# Circuit.net
KiCad netlist of a schematic drawn in EAGLE
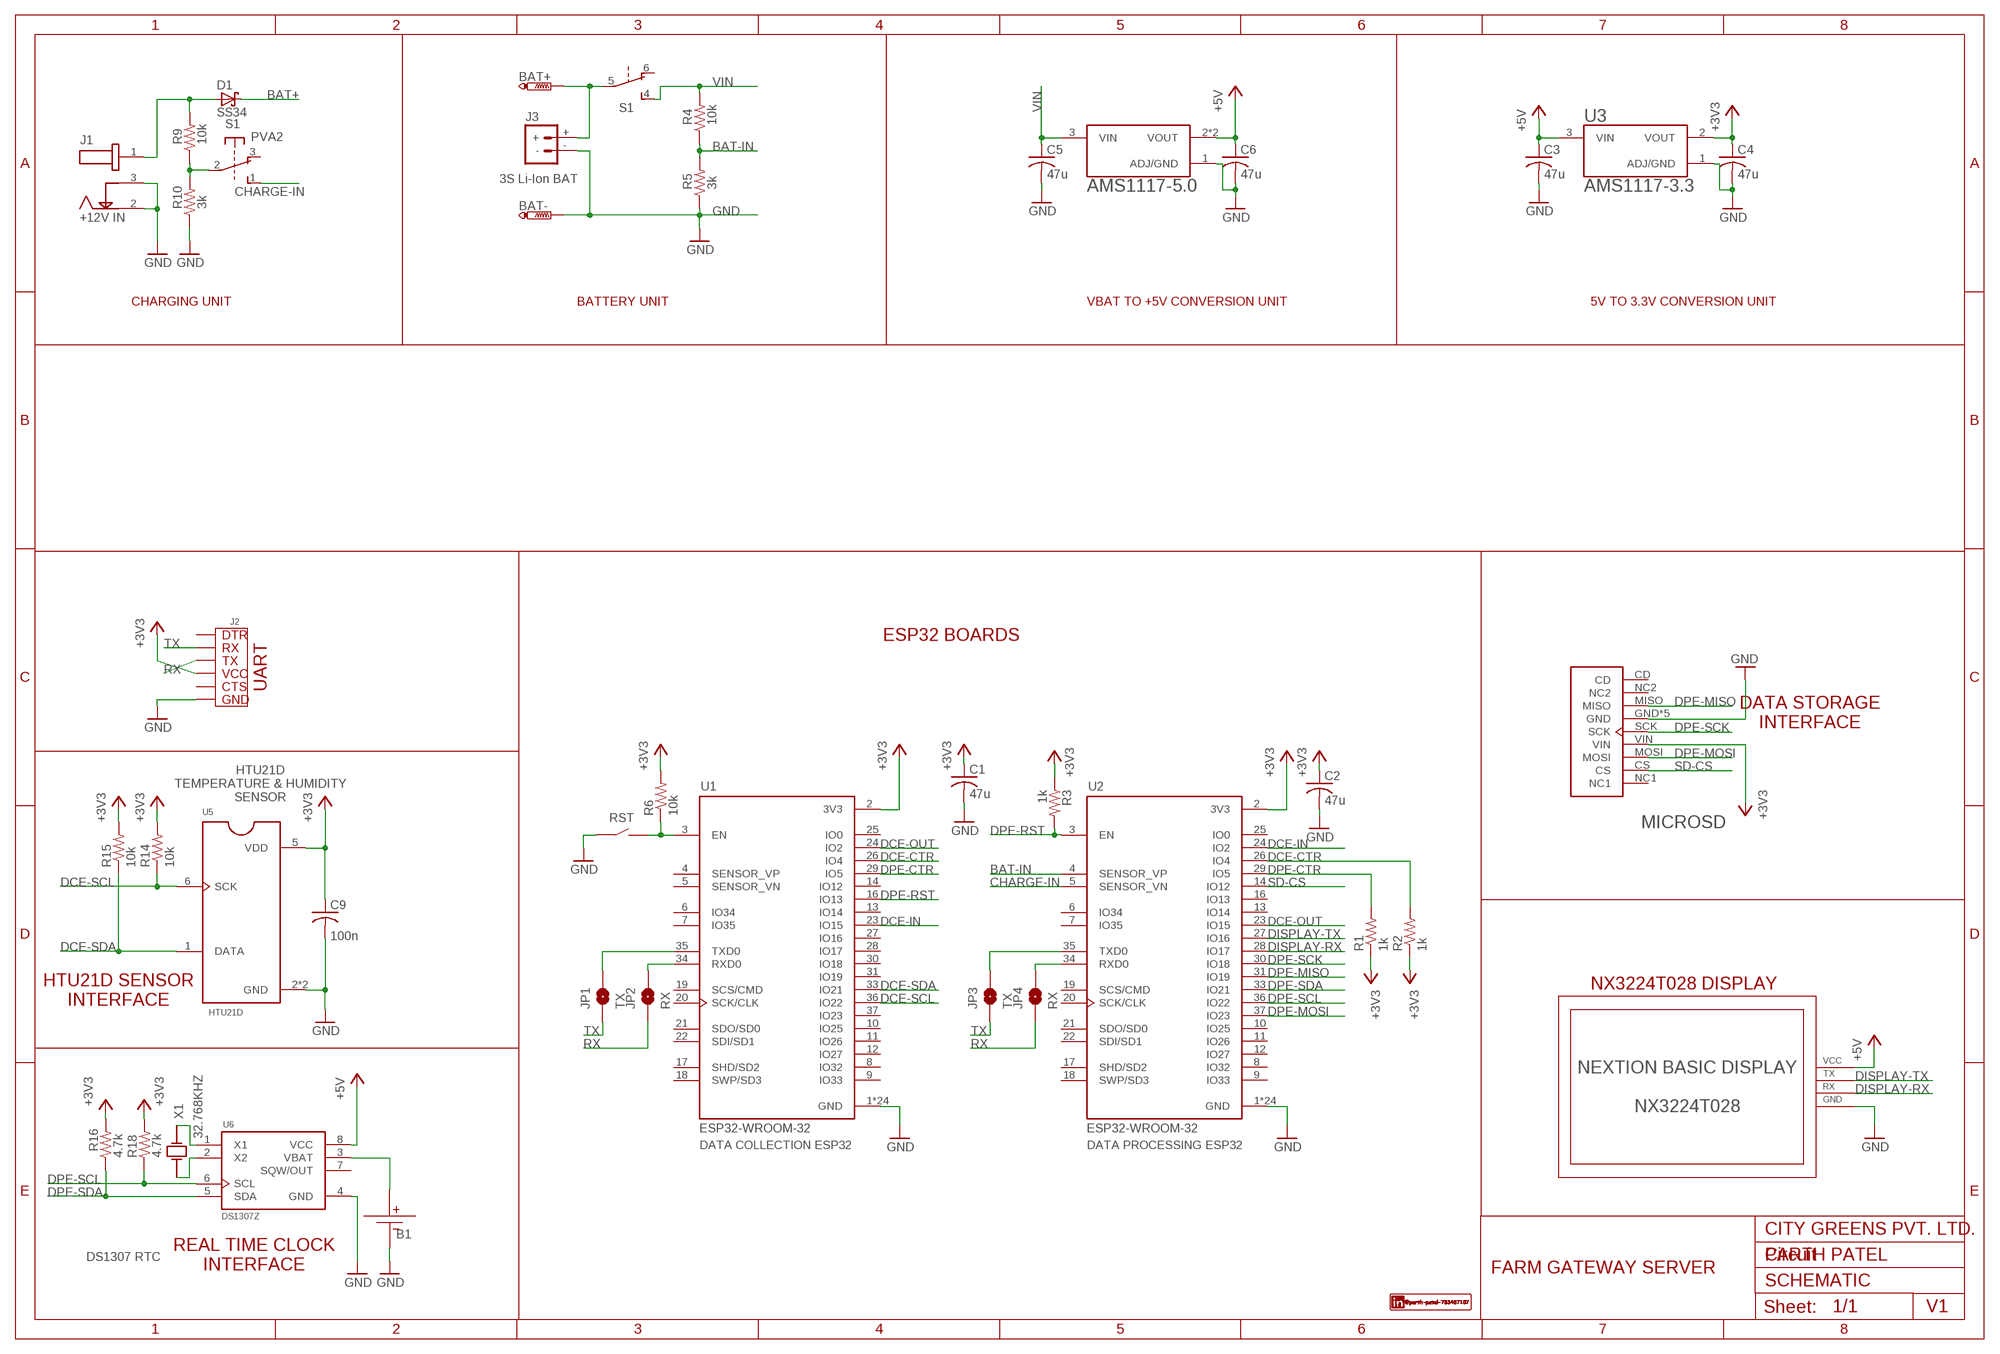
[diagram p0: schematic, sheet 1]

(export (version "E")
  (design (tool "Eeschema 10.0.6"))
  (components
    (comp (ref "B1")
      (value "CR3032-METAL")
      (footprint "eagle-import:CR2032-METAL")
      (libsource (lib "eagle-import") (part "CR3032-METAL"))
    )
    (comp (ref "BAT+")
      (value "PTR1TP20SQ")
      (footprint "eagle-import:TP20SQ")
      (libsource (lib "eagle-import") (part "PTR1TP20SQ"))
    )
    (comp (ref "BAT-")
      (value "PTR1TP20SQ")
      (footprint "eagle-import:TP20SQ")
      (libsource (lib "eagle-import") (part "PTR1TP20SQ"))
    )
    (comp (ref "C1")
      (value "47u")
      (footprint "eagle-import:C0805")
      (libsource (lib "eagle-import") (part "C-USC0805"))
    )
    (comp (ref "C2")
      (value "47u")
      (footprint "eagle-import:C0805")
      (libsource (lib "eagle-import") (part "C-USC0805"))
    )
    (comp (ref "C3")
      (value "47u")
      (footprint "eagle-import:C0805")
      (libsource (lib "eagle-import") (part "C-USC0805"))
    )
    (comp (ref "C4")
      (value "47u")
      (footprint "eagle-import:C0805")
      (libsource (lib "eagle-import") (part "C-USC0805"))
    )
    (comp (ref "C5")
      (value "47u")
      (footprint "eagle-import:C0805")
      (libsource (lib "eagle-import") (part "C-USC0805"))
    )
    (comp (ref "C6")
      (value "47u")
      (footprint "eagle-import:C0805")
      (libsource (lib "eagle-import") (part "C-USC0805"))
    )
    (comp (ref "C9")
      (value "100n")
      (footprint "eagle-import:C0805")
      (libsource (lib "eagle-import") (part "C-USC0805"))
    )
    (comp (ref "D1")
      (value "SS34")
      (footprint "eagle-import:DO214")
      (fields (field (name "MF") "ON Semiconductor"))
      (libsource (lib "eagle-import") (part "SS34"))
    )
    (comp (ref "J1")
      (value "+12V IN")
      (footprint "eagle-import:GCT_DCJ200-10-A-XX-X_REVA")
      (fields (field (name "MF") "Global Connector Technology") (field (name "MP") "DCJ200-10-A-K1-K"))
      (libsource (lib "eagle-import") (part "DCJ200-10-A-XX-X_REVA"))
    )
    (comp (ref "J2")
      (value "UART")
      (footprint "eagle-import:UART")
      (libsource (lib "eagle-import") (part "UART"))
    )
    (comp (ref "J3")
      (value "3S Li-Ion BAT")
      (footprint "eagle-import:DEANS")
      (libsource (lib "eagle-import") (part "BATTERY_CONN_DEANS"))
    )
    (comp (ref "JP1")
      (value "TX")
      (footprint "eagle-import:SMT-JUMPER_2_NO_NO-SILK")
      (libsource (lib "eagle-import") (part "JUMPER-SMT_2_NO_NO-SILK"))
    )
    (comp (ref "JP2")
      (value "RX")
      (footprint "eagle-import:SMT-JUMPER_2_NO_NO-SILK")
      (libsource (lib "eagle-import") (part "JUMPER-SMT_2_NO_NO-SILK"))
    )
    (comp (ref "JP3")
      (value "TX")
      (footprint "eagle-import:SMT-JUMPER_2_NO_NO-SILK")
      (libsource (lib "eagle-import") (part "JUMPER-SMT_2_NO_NO-SILK"))
    )
    (comp (ref "JP4")
      (value "RX")
      (footprint "eagle-import:SMT-JUMPER_2_NO_NO-SILK")
      (libsource (lib "eagle-import") (part "JUMPER-SMT_2_NO_NO-SILK"))
    )
    (comp (ref "MICROSD")
      (value "ST-TF-003A")
      (footprint "eagle-import:SUNTECH_ST-TF-003A")
      (fields (field (name "MF") "Suntech"))
      (libsource (lib "eagle-import") (part "ST-TF-003A"))
    )
    (comp (ref "NX3224T028")
      (value "NX3224T028_011")
      (footprint "eagle-import:NX3224T028_011")
      (libsource (lib "eagle-import") (part "NX3224T028_011"))
    )
    (comp (ref "R1")
      (value "1k")
      (footprint "eagle-import:R0805")
      (libsource (lib "eagle-import") (part "R-US_R0805"))
    )
    (comp (ref "R2")
      (value "1k")
      (footprint "eagle-import:R0805")
      (libsource (lib "eagle-import") (part "R-US_R0805"))
    )
    (comp (ref "R3")
      (value "1k")
      (footprint "eagle-import:R0805")
      (libsource (lib "eagle-import") (part "R-US_R0805"))
    )
    (comp (ref "R4")
      (value "10k")
      (footprint "eagle-import:R0805")
      (libsource (lib "eagle-import") (part "R-US_R0805"))
    )
    (comp (ref "R5")
      (value "3k")
      (footprint "eagle-import:R0805")
      (libsource (lib "eagle-import") (part "R-US_R0805"))
    )
    (comp (ref "R6")
      (value "10k")
      (footprint "eagle-import:R0805")
      (libsource (lib "eagle-import") (part "R-US_R0805"))
    )
    (comp (ref "R9")
      (value "10k")
      (footprint "eagle-import:R0805")
      (libsource (lib "eagle-import") (part "R-US_R0805"))
    )
    (comp (ref "R10")
      (value "3k")
      (footprint "eagle-import:R0805")
      (libsource (lib "eagle-import") (part "R-US_R0805"))
    )
    (comp (ref "R14")
      (value "10k")
      (footprint "eagle-import:R0805")
      (libsource (lib "eagle-import") (part "R-US_R0805"))
    )
    (comp (ref "R15")
      (value "10k")
      (footprint "eagle-import:R0805")
      (libsource (lib "eagle-import") (part "R-US_R0805"))
    )
    (comp (ref "R16")
      (value "4.7k")
      (footprint "eagle-import:R0805")
      (libsource (lib "eagle-import") (part "R-US_R0805"))
    )
    (comp (ref "R18")
      (value "4.7k")
      (footprint "eagle-import:R0805")
      (libsource (lib "eagle-import") (part "R-US_R0805"))
    )
    (comp (ref "RST")
      (value "4.5X4.5-SMD-TACTILE-SWITCH")
      (footprint "eagle-import:SMD-4.5X4.5-TACTILE-PUSH-BUTTON")
      (libsource (lib "eagle-import") (part "4.5X4.5-SMD-TACTILE-SWITCH"))
    )
    (comp (ref "S1")
      (value "PVA2")
      (footprint "eagle-import:PVA2F")
      (libsource (lib "eagle-import") (part "PVA2"))
    )
    (comp (ref "U1")
      (value "ESP32-WROOM-32")
      (footprint "eagle-import:MODULE_ESP32-WROOM-32")
      (fields (field (name "MF") "Espressif Systems"))
      (libsource (lib "eagle-import") (part "ESP32-WROOM-32"))
    )
    (comp (ref "U2")
      (value "ESP32-WROOM-32")
      (footprint "eagle-import:MODULE_ESP32-WROOM-32")
      (fields (field (name "MF") "Espressif Systems"))
      (libsource (lib "eagle-import") (part "ESP32-WROOM-32"))
    )
    (comp (ref "U3")
      (value "AMS1117-3.3")
      (footprint "eagle-import:SOT229P700X180-4N")
      (fields (field (name "MF") "AMD"))
      (libsource (lib "eagle-import") (part "AMS1117-3.3"))
    )
    (comp (ref "U4")
      (value "AMS1117-5.0")
      (footprint "eagle-import:SOT229P700X180-4N")
      (fields (field (name "MF") "Advanced Monolithic Systems"))
      (libsource (lib "eagle-import") (part "AMS1117-5.0"))
    )
    (comp (ref "U5")
      (value "HTU21D")
      (footprint "eagle-import:QFN100P300X300X100-7N")
      (fields (field (name "COMMENT") "CAT-HSC0004") (field (name "MF") "TE Connectivity"))
      (libsource (lib "eagle-import") (part "HTU21D"))
    )
    (comp (ref "U6")
      (value "DS1307Z")
      (footprint "eagle-import:SOIC127P600X175-8N")
      (fields (field (name "MF") "Maxim Integrated"))
      (libsource (lib "eagle-import") (part "DS1307Z"))
    )
    (comp (ref "X1")
      (value "32.768KHZ")
      (footprint "eagle-import:XTAL_AB38T-32.768KHZ")
      (fields (field (name "MF") "Abracon") (field (name "MP") "AB38T-32.768KHZ"))
      (libsource (lib "eagle-import") (part "AB38T-32.768KHZ"))
    )
  )
  (nets
    (net (code "1") (name "+3V3") (class "Default")
      (node (ref "C1") (pin "1") (pinfunction "1_1") (pintype "passive"))
      (node (ref "C2") (pin "1") (pinfunction "1_1") (pintype "passive"))
      (node (ref "C4") (pin "1") (pinfunction "1_1") (pintype "passive"))
      (node (ref "C9") (pin "1") (pinfunction "1_1") (pintype "passive"))
      (node (ref "J2") (pin "VCC") (pinfunction "VCC_VCC") (pintype "bidirectional"))
      (node (ref "MICROSD") (pin "VIN") (pinfunction "VIN_VIN") (pintype "bidirectional"))
      (node (ref "R1") (pin "1") (pinfunction "1_1") (pintype "passive"))
      (node (ref "R14") (pin "2") (pinfunction "2_2") (pintype "passive"))
      (node (ref "R15") (pin "2") (pinfunction "2_2") (pintype "passive"))
      (node (ref "R16") (pin "2") (pinfunction "2_2") (pintype "passive"))
      (node (ref "R18") (pin "2") (pinfunction "2_2") (pintype "passive"))
      (node (ref "R2") (pin "1") (pinfunction "1_1") (pintype "passive"))
      (node (ref "R3") (pin "1") (pinfunction "1_1") (pintype "passive"))
      (node (ref "R6") (pin "2") (pinfunction "2_2") (pintype "passive"))
      (node (ref "U1") (pin "2") (pinfunction "3V3_2") (pintype "power_in"))
      (node (ref "U2") (pin "2") (pinfunction "3V3_2") (pintype "power_in"))
      (node (ref "U3") (pin "2") (pinfunction "VOUT_2") (pintype "output"))
      (node (ref "U5") (pin "5") (pinfunction "VDD_5") (pintype "power_in"))
    )
    (net (code "2") (name "+5V") (class "Default")
      (node (ref "C3") (pin "1") (pinfunction "1_1") (pintype "passive"))
      (node (ref "C6") (pin "1") (pinfunction "1_1") (pintype "passive"))
      (node (ref "NX3224T028") (pin "VCC") (pinfunction "VCC_VCC") (pintype "bidirectional"))
      (node (ref "U3") (pin "3") (pinfunction "VIN_3") (pintype "input"))
      (node (ref "U4") (pin "2") (pinfunction "VOUT_2") (pintype "output"))
      (node (ref "U4") (pin "4") (pinfunction "VOUT_4") (pintype "output"))
      (node (ref "U6") (pin "8") (pinfunction "VCC_8") (pintype "power_in"))
    )
    (net (code "3") (name "/BAT+") (class "Default")
      (node (ref "BAT+") (pin "TP") (pinfunction "TP_TP") (pintype "input"))
      (node (ref "D1") (pin "C") (pinfunction "C_C") (pintype "passive"))
      (node (ref "J3") (pin "+") (pinfunction "+_+") (pintype "passive"))
      (node (ref "S1") (pin "5") (pinfunction "P_5") (pintype "passive"))
    )
    (net (code "4") (name "/BAT-IN") (class "Default")
      (node (ref "R4") (pin "1") (pinfunction "1_1") (pintype "passive"))
      (node (ref "R5") (pin "2") (pinfunction "2_2") (pintype "passive"))
      (node (ref "U2") (pin "4") (pinfunction "SENSOR_VP_4") (pintype "input"))
    )
    (net (code "5") (name "/CHARGE-IN") (class "Default")
      (node (ref "S1") (pin "1") (pinfunction "S_1") (pintype "passive"))
      (node (ref "U2") (pin "5") (pinfunction "SENSOR_VN_5") (pintype "input"))
    )
    (net (code "6") (name "/DCE-CTR") (class "Default")
      (node (ref "R2") (pin "2") (pinfunction "2_2") (pintype "passive"))
      (node (ref "U1") (pin "26") (pinfunction "IO4_26") (pintype "bidirectional"))
      (node (ref "U2") (pin "26") (pinfunction "IO4_26") (pintype "bidirectional"))
    )
    (net (code "7") (name "/DCE-IN") (class "Default")
      (node (ref "U1") (pin "23") (pinfunction "IO15_23") (pintype "bidirectional"))
      (node (ref "U2") (pin "24") (pinfunction "IO2_24") (pintype "bidirectional"))
    )
    (net (code "8") (name "/DCE-OUT") (class "Default")
      (node (ref "U1") (pin "24") (pinfunction "IO2_24") (pintype "bidirectional"))
      (node (ref "U2") (pin "23") (pinfunction "IO15_23") (pintype "bidirectional"))
    )
    (net (code "9") (name "/DCE-SCL") (class "Default")
      (node (ref "R14") (pin "1") (pinfunction "1_1") (pintype "passive"))
      (node (ref "U1") (pin "36") (pinfunction "IO22_36") (pintype "bidirectional"))
      (node (ref "U5") (pin "6") (pinfunction "SCK_6") (pintype "input"))
    )
    (net (code "10") (name "/DCE-SDA") (class "Default")
      (node (ref "R15") (pin "1") (pinfunction "1_1") (pintype "passive"))
      (node (ref "U1") (pin "33") (pinfunction "IO21_33") (pintype "bidirectional"))
      (node (ref "U5") (pin "1") (pinfunction "DATA_1") (pintype "bidirectional"))
    )
    (net (code "11") (name "/DISPLAY-RX") (class "Default")
      (node (ref "NX3224T028") (pin "RX") (pinfunction "RX_RX") (pintype "bidirectional"))
      (node (ref "U2") (pin "28") (pinfunction "IO17_28") (pintype "bidirectional"))
    )
    (net (code "12") (name "/DISPLAY-TX") (class "Default")
      (node (ref "NX3224T028") (pin "TX") (pinfunction "TX_TX") (pintype "bidirectional"))
      (node (ref "U2") (pin "27") (pinfunction "IO16_27") (pintype "bidirectional"))
    )
    (net (code "13") (name "/DPE-CTR") (class "Default")
      (node (ref "R1") (pin "2") (pinfunction "2_2") (pintype "passive"))
      (node (ref "U1") (pin "29") (pinfunction "IO5_29") (pintype "bidirectional"))
      (node (ref "U2") (pin "29") (pinfunction "IO5_29") (pintype "bidirectional"))
    )
    (net (code "14") (name "/DPE-MISO") (class "Default")
      (node (ref "MICROSD") (pin "MISO") (pinfunction "MISO_MISO") (pintype "bidirectional"))
      (node (ref "U2") (pin "31") (pinfunction "IO19_31") (pintype "bidirectional"))
    )
    (net (code "15") (name "/DPE-MOSI") (class "Default")
      (node (ref "MICROSD") (pin "MOSI") (pinfunction "MOSI_MOSI") (pintype "input"))
      (node (ref "U2") (pin "37") (pinfunction "IO23_37") (pintype "bidirectional"))
    )
    (net (code "16") (name "/DPE-RST") (class "Default")
      (node (ref "R3") (pin "2") (pinfunction "2_2") (pintype "passive"))
      (node (ref "U1") (pin "16") (pinfunction "IO13_16") (pintype "bidirectional"))
      (node (ref "U2") (pin "3") (pinfunction "EN_3") (pintype "input"))
    )
    (net (code "17") (name "/DPE-SCK") (class "Default")
      (node (ref "MICROSD") (pin "SCK") (pinfunction "SCK_SCK") (pintype "input"))
      (node (ref "U2") (pin "30") (pinfunction "IO18_30") (pintype "bidirectional"))
    )
    (net (code "18") (name "/DPE-SCL") (class "Default")
      (node (ref "R18") (pin "1") (pinfunction "1_1") (pintype "passive"))
      (node (ref "U2") (pin "36") (pinfunction "IO22_36") (pintype "bidirectional"))
      (node (ref "U6") (pin "6") (pinfunction "SCL_6") (pintype "input"))
    )
    (net (code "19") (name "/DPE-SDA") (class "Default")
      (node (ref "R16") (pin "1") (pinfunction "1_1") (pintype "passive"))
      (node (ref "U2") (pin "33") (pinfunction "IO21_33") (pintype "bidirectional"))
      (node (ref "U6") (pin "5") (pinfunction "SDA_5") (pintype "bidirectional"))
    )
    (net (code "20") (name "/RX") (class "Default")
      (node (ref "J2") (pin "TX") (pinfunction "TX_TX") (pintype "bidirectional"))
      (node (ref "JP2") (pin "1") (pinfunction "1_1") (pintype "passive"))
      (node (ref "JP4") (pin "1") (pinfunction "1_1") (pintype "passive"))
    )
    (net (code "21") (name "/SD-CS") (class "Default")
      (node (ref "MICROSD") (pin "CS") (pinfunction "CS_CS") (pintype "bidirectional"))
      (node (ref "U2") (pin "14") (pinfunction "IO12_14") (pintype "bidirectional"))
    )
    (net (code "22") (name "/TX") (class "Default")
      (node (ref "J2") (pin "RX") (pinfunction "RX_RX") (pintype "bidirectional"))
      (node (ref "JP1") (pin "1") (pinfunction "1_1") (pintype "passive"))
      (node (ref "JP3") (pin "1") (pinfunction "1_1") (pintype "passive"))
    )
    (net (code "23") (name "/VIN") (class "Default")
      (node (ref "C5") (pin "1") (pinfunction "1_1") (pintype "passive"))
      (node (ref "R4") (pin "2") (pinfunction "2_2") (pintype "passive"))
      (node (ref "S1") (pin "4") (pinfunction "S_4") (pintype "passive"))
      (node (ref "U4") (pin "3") (pinfunction "VIN_3") (pintype "input"))
    )
    (net (code "24") (name "GND") (class "Default")
      (node (ref "B1") (pin "-VE1") (pinfunction "-VE_-VE1") (pintype "bidirectional"))
      (node (ref "B1") (pin "-VE2") (pinfunction "-VE_-VE2") (pintype "bidirectional"))
      (node (ref "BAT-") (pin "TP") (pinfunction "TP_TP") (pintype "input"))
      (node (ref "C1") (pin "2") (pinfunction "2_2") (pintype "passive"))
      (node (ref "C2") (pin "2") (pinfunction "2_2") (pintype "passive"))
      (node (ref "C3") (pin "2") (pinfunction "2_2") (pintype "passive"))
      (node (ref "C4") (pin "2") (pinfunction "2_2") (pintype "passive"))
      (node (ref "C5") (pin "2") (pinfunction "2_2") (pintype "passive"))
      (node (ref "C6") (pin "2") (pinfunction "2_2") (pintype "passive"))
      (node (ref "C9") (pin "2") (pinfunction "2_2") (pintype "passive"))
      (node (ref "J1") (pin "2") (pinfunction "2_2") (pintype "passive"))
      (node (ref "J1") (pin "3") (pinfunction "3_3") (pintype "passive"))
      (node (ref "J2") (pin "GND") (pinfunction "GND_GND") (pintype "bidirectional"))
      (node (ref "J3") (pin "-") (pinfunction "-_-") (pintype "passive"))
      (node (ref "MICROSD") (pin "GND") (pinfunction "GND_GND") (pintype "power_in"))
      (node (ref "MICROSD") (pin "GND2") (pinfunction "GND_GND2") (pintype "power_in"))
      (node (ref "MICROSD") (pin "GND3") (pinfunction "GND_GND3") (pintype "power_in"))
      (node (ref "MICROSD") (pin "GND4") (pinfunction "GND_GND4") (pintype "power_in"))
      (node (ref "MICROSD") (pin "GND5") (pinfunction "GND_GND5") (pintype "power_in"))
      (node (ref "NX3224T028") (pin "GND") (pinfunction "GND_GND") (pintype "bidirectional"))
      (node (ref "R10") (pin "1") (pinfunction "1_1") (pintype "passive"))
      (node (ref "R5") (pin "1") (pinfunction "1_1") (pintype "passive"))
      (node (ref "RST") (pin "1.1") (pinfunction "S1_1.1") (pintype "bidirectional"))
      (node (ref "RST") (pin "1.2") (pinfunction "S1_1.2") (pintype "bidirectional"))
      (node (ref "U1") (pin "1") (pinfunction "GND_1") (pintype "power_in"))
      (node (ref "U1") (pin "15") (pinfunction "GND_15") (pintype "power_in"))
      (node (ref "U1") (pin "38") (pinfunction "GND_38") (pintype "power_in"))
      (node (ref "U1") (pin "39_1") (pinfunction "GND_39_1") (pintype "power_in"))
      (node (ref "U1") (pin "39_10") (pinfunction "GND_39_10") (pintype "power_in"))
      (node (ref "U1") (pin "39_11") (pinfunction "GND_39_11") (pintype "power_in"))
      (node (ref "U1") (pin "39_12") (pinfunction "GND_39_12") (pintype "power_in"))
      (node (ref "U1") (pin "39_13") (pinfunction "GND_39_13") (pintype "power_in"))
      (node (ref "U1") (pin "39_14") (pinfunction "GND_39_14") (pintype "power_in"))
      (node (ref "U1") (pin "39_15") (pinfunction "GND_39_15") (pintype "power_in"))
      (node (ref "U1") (pin "39_16") (pinfunction "GND_39_16") (pintype "power_in"))
      (node (ref "U1") (pin "39_17") (pinfunction "GND_39_17") (pintype "power_in"))
      (node (ref "U1") (pin "39_18") (pinfunction "GND_39_18") (pintype "power_in"))
      (node (ref "U1") (pin "39_19") (pinfunction "GND_39_19") (pintype "power_in"))
      (node (ref "U1") (pin "39_2") (pinfunction "GND_39_2") (pintype "power_in"))
      (node (ref "U1") (pin "39_20") (pinfunction "GND_39_20") (pintype "power_in"))
      (node (ref "U1") (pin "39_21") (pinfunction "GND_39_21") (pintype "power_in"))
      (node (ref "U1") (pin "39_3") (pinfunction "GND_39_3") (pintype "power_in"))
      (node (ref "U1") (pin "39_4") (pinfunction "GND_39_4") (pintype "power_in"))
      (node (ref "U1") (pin "39_5") (pinfunction "GND_39_5") (pintype "power_in"))
      (node (ref "U1") (pin "39_6") (pinfunction "GND_39_6") (pintype "power_in"))
      (node (ref "U1") (pin "39_7") (pinfunction "GND_39_7") (pintype "power_in"))
      (node (ref "U1") (pin "39_8") (pinfunction "GND_39_8") (pintype "power_in"))
      (node (ref "U1") (pin "39_9") (pinfunction "GND_39_9") (pintype "power_in"))
      (node (ref "U2") (pin "1") (pinfunction "GND_1") (pintype "power_in"))
      (node (ref "U2") (pin "15") (pinfunction "GND_15") (pintype "power_in"))
      (node (ref "U2") (pin "38") (pinfunction "GND_38") (pintype "power_in"))
      (node (ref "U2") (pin "39_1") (pinfunction "GND_39_1") (pintype "power_in"))
      (node (ref "U2") (pin "39_10") (pinfunction "GND_39_10") (pintype "power_in"))
      (node (ref "U2") (pin "39_11") (pinfunction "GND_39_11") (pintype "power_in"))
      (node (ref "U2") (pin "39_12") (pinfunction "GND_39_12") (pintype "power_in"))
      (node (ref "U2") (pin "39_13") (pinfunction "GND_39_13") (pintype "power_in"))
      (node (ref "U2") (pin "39_14") (pinfunction "GND_39_14") (pintype "power_in"))
      (node (ref "U2") (pin "39_15") (pinfunction "GND_39_15") (pintype "power_in"))
      (node (ref "U2") (pin "39_16") (pinfunction "GND_39_16") (pintype "power_in"))
      (node (ref "U2") (pin "39_17") (pinfunction "GND_39_17") (pintype "power_in"))
      (node (ref "U2") (pin "39_18") (pinfunction "GND_39_18") (pintype "power_in"))
      (node (ref "U2") (pin "39_19") (pinfunction "GND_39_19") (pintype "power_in"))
      (node (ref "U2") (pin "39_2") (pinfunction "GND_39_2") (pintype "power_in"))
      (node (ref "U2") (pin "39_20") (pinfunction "GND_39_20") (pintype "power_in"))
      (node (ref "U2") (pin "39_21") (pinfunction "GND_39_21") (pintype "power_in"))
      (node (ref "U2") (pin "39_3") (pinfunction "GND_39_3") (pintype "power_in"))
      (node (ref "U2") (pin "39_4") (pinfunction "GND_39_4") (pintype "power_in"))
      (node (ref "U2") (pin "39_5") (pinfunction "GND_39_5") (pintype "power_in"))
      (node (ref "U2") (pin "39_6") (pinfunction "GND_39_6") (pintype "power_in"))
      (node (ref "U2") (pin "39_7") (pinfunction "GND_39_7") (pintype "power_in"))
      (node (ref "U2") (pin "39_8") (pinfunction "GND_39_8") (pintype "power_in"))
      (node (ref "U2") (pin "39_9") (pinfunction "GND_39_9") (pintype "power_in"))
      (node (ref "U3") (pin "1") (pinfunction "ADJ/GND_1") (pintype "power_in"))
      (node (ref "U4") (pin "1") (pinfunction "ADJ/GND_1") (pintype "power_in"))
      (node (ref "U5") (pin "2") (pinfunction "GND_2") (pintype "passive"))
      (node (ref "U5") (pin "PAD") (pinfunction "GND_PAD") (pintype "passive"))
      (node (ref "U6") (pin "4") (pinfunction "GND_4") (pintype "power_in"))
    )
    (net (code "25") (name "Net-(D1-PadA)") (class "Default")
      (node (ref "D1") (pin "A") (pinfunction "A_A") (pintype "passive"))
      (node (ref "J1") (pin "1") (pinfunction "1_1") (pintype "passive"))
      (node (ref "R9") (pin "2") (pinfunction "2_2") (pintype "passive"))
    )
    (net (code "26") (name "Net-(S1A-P)") (class "Default")
      (node (ref "R10") (pin "2") (pinfunction "2_2") (pintype "passive"))
      (node (ref "R9") (pin "1") (pinfunction "1_1") (pintype "passive"))
      (node (ref "S1") (pin "2") (pinfunction "P_2") (pintype "passive"))
    )
    (net (code "27") (name "Net-(U1-EN)") (class "Default")
      (node (ref "R6") (pin "1") (pinfunction "1_1") (pintype "passive"))
      (node (ref "RST") (pin "2.1") (pinfunction "S2_2.1") (pintype "bidirectional"))
      (node (ref "RST") (pin "2.2") (pinfunction "S2_2.2") (pintype "bidirectional"))
      (node (ref "U1") (pin "3") (pinfunction "EN_3") (pintype "input"))
    )
    (net (code "28") (name "Net-(U1-RXD0)") (class "Default")
      (node (ref "JP2") (pin "2") (pinfunction "2_2") (pintype "passive"))
      (node (ref "U1") (pin "34") (pinfunction "RXD0_34") (pintype "bidirectional"))
    )
    (net (code "29") (name "Net-(U1-TXD0)") (class "Default")
      (node (ref "JP1") (pin "2") (pinfunction "2_2") (pintype "passive"))
      (node (ref "U1") (pin "35") (pinfunction "TXD0_35") (pintype "bidirectional"))
    )
    (net (code "30") (name "Net-(U2-RXD0)") (class "Default")
      (node (ref "JP4") (pin "2") (pinfunction "2_2") (pintype "passive"))
      (node (ref "U2") (pin "34") (pinfunction "RXD0_34") (pintype "bidirectional"))
    )
    (net (code "31") (name "Net-(U2-TXD0)") (class "Default")
      (node (ref "JP3") (pin "2") (pinfunction "2_2") (pintype "passive"))
      (node (ref "U2") (pin "35") (pinfunction "TXD0_35") (pintype "bidirectional"))
    )
    (net (code "32") (name "Net-(U6-VBAT)") (class "Default")
      (node (ref "B1") (pin "+VE") (pinfunction "+VE_+VE") (pintype "bidirectional"))
      (node (ref "U6") (pin "3") (pinfunction "VBAT_3") (pintype "power_in"))
    )
    (net (code "33") (name "Net-(U6-X1)") (class "Default")
      (node (ref "U6") (pin "1") (pinfunction "X1_1") (pintype "input"))
      (node (ref "X1") (pin "2") (pinfunction "2_2") (pintype "passive"))
    )
    (net (code "34") (name "Net-(U6-X2)") (class "Default")
      (node (ref "U6") (pin "2") (pinfunction "X2_2") (pintype "input"))
      (node (ref "X1") (pin "1") (pinfunction "1_1") (pintype "passive"))
    )
    (net (code "35") (name "unconnected-(J2-PadCTS)") (class "Default")
      (node (ref "J2") (pin "CTS") (pinfunction "CTS_CTS") (pintype "bidirectional"))
    )
    (net (code "36") (name "unconnected-(J2-PadDTR)") (class "Default")
      (node (ref "J2") (pin "DTR") (pinfunction "DTR_DTR") (pintype "bidirectional"))
    )
    (net (code "37") (name "unconnected-(MICROSD-PadCD)") (class "Default")
      (node (ref "MICROSD") (pin "CD") (pinfunction "CD_CD") (pintype "bidirectional"))
    )
    (net (code "38") (name "unconnected-(MICROSD-PadNC1)") (class "Default")
      (node (ref "MICROSD") (pin "NC1") (pinfunction "NC1_NC1") (pintype "bidirectional"))
    )
    (net (code "39") (name "unconnected-(MICROSD-PadNC2)") (class "Default")
      (node (ref "MICROSD") (pin "NC2") (pinfunction "NC2_NC2") (pintype "passive"))
    )
    (net (code "40") (name "unconnected-(S1A-O-Pad3)") (class "Default")
      (node (ref "S1") (pin "3") (pinfunction "O_3") (pintype "passive"))
    )
    (net (code "41") (name "unconnected-(S1B-O-Pad6)") (class "Default")
      (node (ref "S1") (pin "6") (pinfunction "O_6") (pintype "passive"))
    )
    (net (code "42") (name "unconnected-(U1-IO0-Pad25)") (class "Default")
      (node (ref "U1") (pin "25") (pinfunction "IO0_25") (pintype "bidirectional"))
    )
    (net (code "43") (name "unconnected-(U1-IO12-Pad14)") (class "Default")
      (node (ref "U1") (pin "14") (pinfunction "IO12_14") (pintype "bidirectional"))
    )
    (net (code "44") (name "unconnected-(U1-IO14-Pad13)") (class "Default")
      (node (ref "U1") (pin "13") (pinfunction "IO14_13") (pintype "bidirectional"))
    )
    (net (code "45") (name "unconnected-(U1-IO16-Pad27)") (class "Default")
      (node (ref "U1") (pin "27") (pinfunction "IO16_27") (pintype "bidirectional"))
    )
    (net (code "46") (name "unconnected-(U1-IO17-Pad28)") (class "Default")
      (node (ref "U1") (pin "28") (pinfunction "IO17_28") (pintype "bidirectional"))
    )
    (net (code "47") (name "unconnected-(U1-IO18-Pad30)") (class "Default")
      (node (ref "U1") (pin "30") (pinfunction "IO18_30") (pintype "bidirectional"))
    )
    (net (code "48") (name "unconnected-(U1-IO19-Pad31)") (class "Default")
      (node (ref "U1") (pin "31") (pinfunction "IO19_31") (pintype "bidirectional"))
    )
    (net (code "49") (name "unconnected-(U1-IO23-Pad37)") (class "Default")
      (node (ref "U1") (pin "37") (pinfunction "IO23_37") (pintype "bidirectional"))
    )
    (net (code "50") (name "unconnected-(U1-IO25-Pad10)") (class "Default")
      (node (ref "U1") (pin "10") (pinfunction "IO25_10") (pintype "bidirectional"))
    )
    (net (code "51") (name "unconnected-(U1-IO26-Pad11)") (class "Default")
      (node (ref "U1") (pin "11") (pinfunction "IO26_11") (pintype "bidirectional"))
    )
    (net (code "52") (name "unconnected-(U1-IO27-Pad12)") (class "Default")
      (node (ref "U1") (pin "12") (pinfunction "IO27_12") (pintype "bidirectional"))
    )
    (net (code "53") (name "unconnected-(U1-IO32-Pad8)") (class "Default")
      (node (ref "U1") (pin "8") (pinfunction "IO32_8") (pintype "bidirectional"))
    )
    (net (code "54") (name "unconnected-(U1-IO33-Pad9)") (class "Default")
      (node (ref "U1") (pin "9") (pinfunction "IO33_9") (pintype "bidirectional"))
    )
    (net (code "55") (name "unconnected-(U1-IO34-Pad6)") (class "Default")
      (node (ref "U1") (pin "6") (pinfunction "IO34_6") (pintype "input"))
    )
    (net (code "56") (name "unconnected-(U1-IO35-Pad7)") (class "Default")
      (node (ref "U1") (pin "7") (pinfunction "IO35_7") (pintype "input"))
    )
    (net (code "57") (name "unconnected-(U1-SCK{slash}CLK-Pad20)") (class "Default")
      (node (ref "U1") (pin "20") (pinfunction "SCK/CLK_20") (pintype "bidirectional"))
    )
    (net (code "58") (name "unconnected-(U1-SCS{slash}CMD-Pad19)") (class "Default")
      (node (ref "U1") (pin "19") (pinfunction "SCS/CMD_19") (pintype "bidirectional"))
    )
    (net (code "59") (name "unconnected-(U1-SDI{slash}SD1-Pad22)") (class "Default")
      (node (ref "U1") (pin "22") (pinfunction "SDI/SD1_22") (pintype "bidirectional"))
    )
    (net (code "60") (name "unconnected-(U1-SDO{slash}SD0-Pad21)") (class "Default")
      (node (ref "U1") (pin "21") (pinfunction "SDO/SD0_21") (pintype "bidirectional"))
    )
    (net (code "61") (name "unconnected-(U1-SENSOR_VN-Pad5)") (class "Default")
      (node (ref "U1") (pin "5") (pinfunction "SENSOR_VN_5") (pintype "input"))
    )
    (net (code "62") (name "unconnected-(U1-SENSOR_VP-Pad4)") (class "Default")
      (node (ref "U1") (pin "4") (pinfunction "SENSOR_VP_4") (pintype "input"))
    )
    (net (code "63") (name "unconnected-(U1-SHD{slash}SD2-Pad17)") (class "Default")
      (node (ref "U1") (pin "17") (pinfunction "SHD/SD2_17") (pintype "bidirectional"))
    )
    (net (code "64") (name "unconnected-(U1-SWP{slash}SD3-Pad18)") (class "Default")
      (node (ref "U1") (pin "18") (pinfunction "SWP/SD3_18") (pintype "bidirectional"))
    )
    (net (code "65") (name "unconnected-(U2-IO0-Pad25)") (class "Default")
      (node (ref "U2") (pin "25") (pinfunction "IO0_25") (pintype "bidirectional"))
    )
    (net (code "66") (name "unconnected-(U2-IO13-Pad16)") (class "Default")
      (node (ref "U2") (pin "16") (pinfunction "IO13_16") (pintype "bidirectional"))
    )
    (net (code "67") (name "unconnected-(U2-IO14-Pad13)") (class "Default")
      (node (ref "U2") (pin "13") (pinfunction "IO14_13") (pintype "bidirectional"))
    )
    (net (code "68") (name "unconnected-(U2-IO25-Pad10)") (class "Default")
      (node (ref "U2") (pin "10") (pinfunction "IO25_10") (pintype "bidirectional"))
    )
    (net (code "69") (name "unconnected-(U2-IO26-Pad11)") (class "Default")
      (node (ref "U2") (pin "11") (pinfunction "IO26_11") (pintype "bidirectional"))
    )
    (net (code "70") (name "unconnected-(U2-IO27-Pad12)") (class "Default")
      (node (ref "U2") (pin "12") (pinfunction "IO27_12") (pintype "bidirectional"))
    )
    (net (code "71") (name "unconnected-(U2-IO32-Pad8)") (class "Default")
      (node (ref "U2") (pin "8") (pinfunction "IO32_8") (pintype "bidirectional"))
    )
    (net (code "72") (name "unconnected-(U2-IO33-Pad9)") (class "Default")
      (node (ref "U2") (pin "9") (pinfunction "IO33_9") (pintype "bidirectional"))
    )
    (net (code "73") (name "unconnected-(U2-IO34-Pad6)") (class "Default")
      (node (ref "U2") (pin "6") (pinfunction "IO34_6") (pintype "input"))
    )
    (net (code "74") (name "unconnected-(U2-IO35-Pad7)") (class "Default")
      (node (ref "U2") (pin "7") (pinfunction "IO35_7") (pintype "input"))
    )
    (net (code "75") (name "unconnected-(U2-SCK{slash}CLK-Pad20)") (class "Default")
      (node (ref "U2") (pin "20") (pinfunction "SCK/CLK_20") (pintype "bidirectional"))
    )
    (net (code "76") (name "unconnected-(U2-SCS{slash}CMD-Pad19)") (class "Default")
      (node (ref "U2") (pin "19") (pinfunction "SCS/CMD_19") (pintype "bidirectional"))
    )
    (net (code "77") (name "unconnected-(U2-SDI{slash}SD1-Pad22)") (class "Default")
      (node (ref "U2") (pin "22") (pinfunction "SDI/SD1_22") (pintype "bidirectional"))
    )
    (net (code "78") (name "unconnected-(U2-SDO{slash}SD0-Pad21)") (class "Default")
      (node (ref "U2") (pin "21") (pinfunction "SDO/SD0_21") (pintype "bidirectional"))
    )
    (net (code "79") (name "unconnected-(U2-SHD{slash}SD2-Pad17)") (class "Default")
      (node (ref "U2") (pin "17") (pinfunction "SHD/SD2_17") (pintype "bidirectional"))
    )
    (net (code "80") (name "unconnected-(U2-SWP{slash}SD3-Pad18)") (class "Default")
      (node (ref "U2") (pin "18") (pinfunction "SWP/SD3_18") (pintype "bidirectional"))
    )
    (net (code "81") (name "unconnected-(U6-SQW{slash}OUT-Pad7)") (class "Default")
      (node (ref "U6") (pin "7") (pinfunction "SQW/OUT_7") (pintype "output"))
    )
  )
)
